# IO_board.net
KiCad netlist of a schematic drawn in Altium Designer
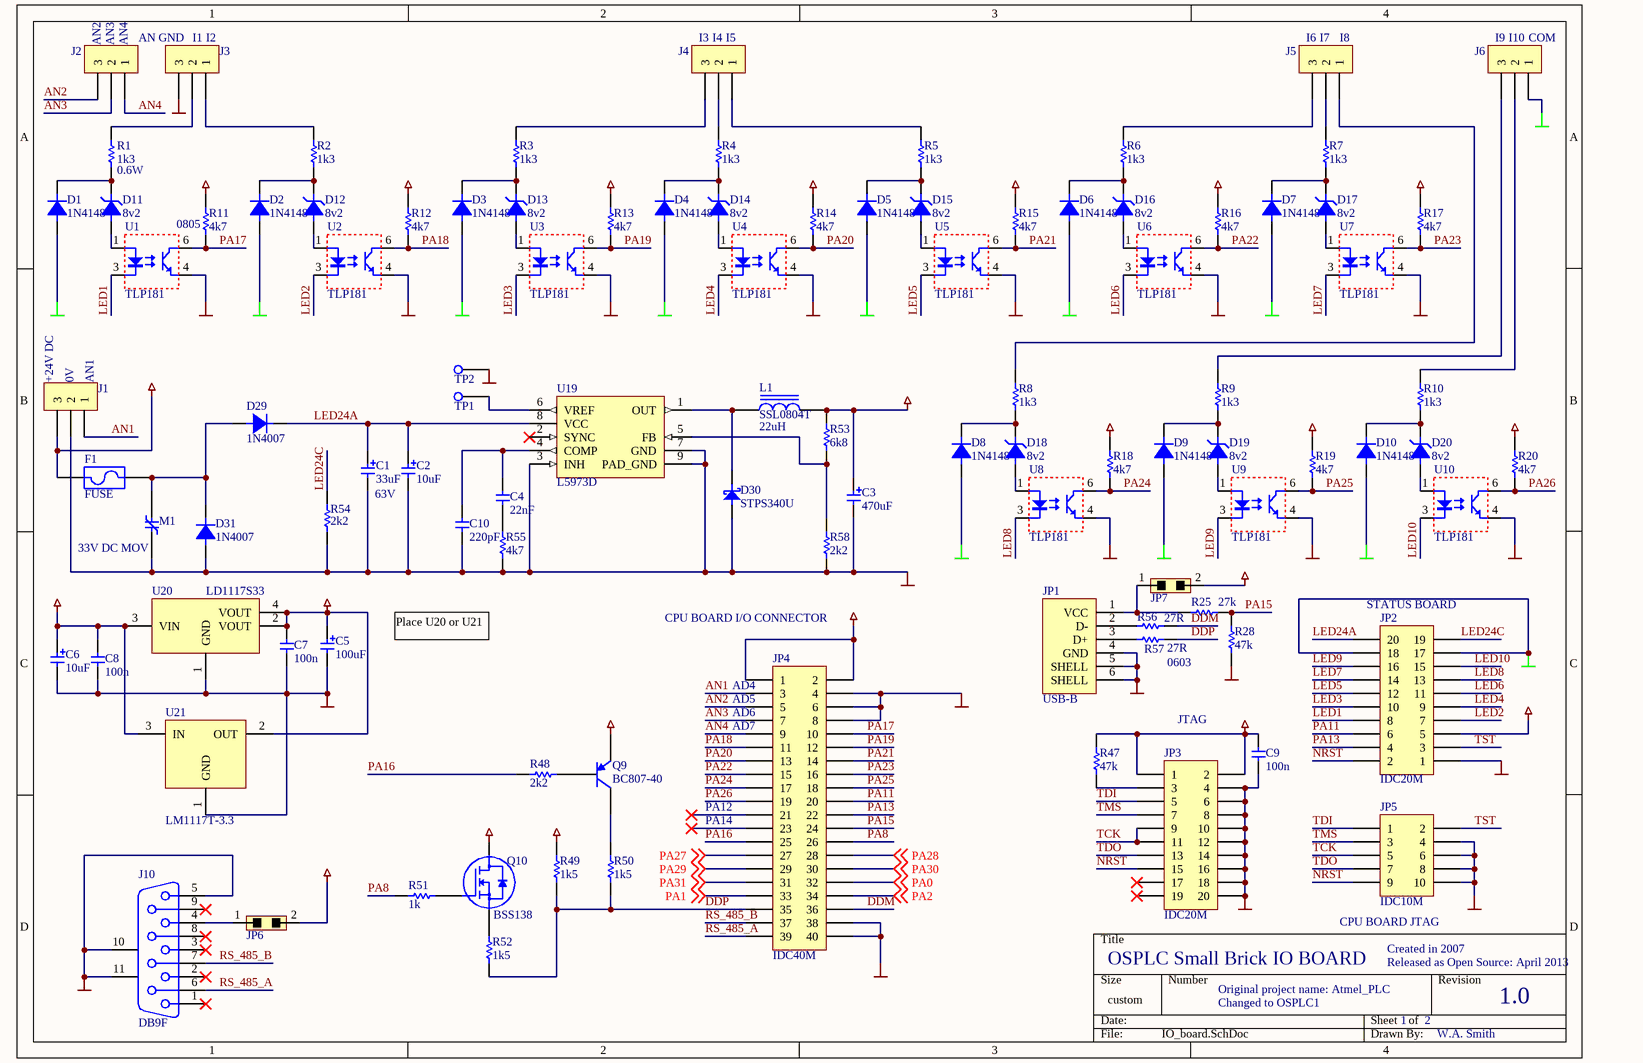
[diagram p0: IO_board.SchDoc]

(export (version "E")
  (design (tool "Eeschema 10.0.6"))
  (components
    (comp (ref "C1")
      (value "63V")
      (footprint "CAP_100_RP")
      (description "Electrolytic cap, 100 mil pitch")
      (fields (field (name "ALTIUM_VALUE") "33uF"))
      (libsource (lib "Integrated Comp_lib") (part "CAP_100_RP"))
    )
    (comp (ref "C2")
      (value "CAP_100_RP")
      (footprint "CAP_100_RP")
      (description "Electrolytic cap, 100 mil pitch")
      (fields (field (name "ALTIUM_VALUE") "10uF"))
      (libsource (lib "Integrated Comp_lib") (part "CAP_100_RP"))
    )
    (comp (ref "C3")
      (value "CAP_200_RP")
      (footprint "CAP_200_RP")
      (description "Radial Electrolytic Capacitor, 200 thou pin spacing")
      (fields (field (name "ALTIUM_VALUE") "470uF"))
      (libsource (lib "Integrated Comp_lib") (part "CAP_200_RP"))
    )
    (comp (ref "C4")
      (value "0805")
      (footprint "0805")
      (description "0805 footprint non-polarised capacitor")
      (fields (field (name "ALTIUM_VALUE") "22nF"))
      (libsource (lib "Integrated Comp_lib") (part "CAP_0805"))
    )
    (comp (ref "C5")
      (value "CAP_100_RP")
      (footprint "CAP_100_RP")
      (description "Electrolytic cap, 100 mil pitch")
      (fields (field (name "ALTIUM_VALUE") "100uF"))
      (libsource (lib "Integrated Comp_lib") (part "CAP_100_RP"))
    )
    (comp (ref "C6")
      (value "CAP_100_RP")
      (footprint "CAP_100_RP")
      (description "Electrolytic cap, 100 mil pitch")
      (fields (field (name "ALTIUM_VALUE") "10uF"))
      (libsource (lib "Integrated Comp_lib") (part "CAP_100_RP"))
    )
    (comp (ref "C7")
      (value "0805")
      (footprint "0805")
      (description "0805 footprint non-polarised capacitor")
      (fields (field (name "ALTIUM_VALUE") "100n"))
      (libsource (lib "Integrated Comp_lib") (part "CAP_0805"))
    )
    (comp (ref "C8")
      (value "0805")
      (footprint "0805")
      (description "0805 footprint non-polarised capacitor")
      (fields (field (name "ALTIUM_VALUE") "100n"))
      (libsource (lib "Integrated Comp_lib") (part "CAP_0805"))
    )
    (comp (ref "C9")
      (value "0603")
      (footprint "0603")
      (description "0603 footprint non-polorised capacitor")
      (fields (field (name "ALTIUM_VALUE") "100n"))
      (libsource (lib "Integrated Comp_lib") (part "CAP_0603"))
    )
    (comp (ref "C10")
      (value "0805")
      (footprint "0805")
      (description "0805 footprint non-polarised capacitor")
      (fields (field (name "ALTIUM_VALUE") "220pF"))
      (libsource (lib "Integrated Comp_lib") (part "CAP_0805"))
    )
    (comp (ref "D1")
      (value "1N4148_RAD")
      (footprint "DIODE_RAD_2.5MM")
      (description "Small signal diode")
      (fields (field (name "ALTIUM_VALUE") "1N4148"))
      (libsource (lib "ARM_projects") (part "1N4148"))
    )
    (comp (ref "D2")
      (value "1N4148_RAD")
      (footprint "DIODE_RAD_2.5MM")
      (description "Small signal diode")
      (fields (field (name "ALTIUM_VALUE") "1N4148"))
      (libsource (lib "ARM_projects") (part "1N4148"))
    )
    (comp (ref "D3")
      (value "1N4148_RAD")
      (footprint "DIODE_RAD_2.5MM")
      (description "Small signal diode")
      (fields (field (name "ALTIUM_VALUE") "1N4148"))
      (libsource (lib "ARM_projects") (part "1N4148"))
    )
    (comp (ref "D4")
      (value "1N4148_RAD")
      (footprint "DIODE_RAD_2.5MM")
      (description "Small signal diode")
      (fields (field (name "ALTIUM_VALUE") "1N4148"))
      (libsource (lib "ARM_projects") (part "1N4148"))
    )
    (comp (ref "D5")
      (value "1N4148_RAD")
      (footprint "DIODE_RAD_2.5MM")
      (description "Small signal diode")
      (fields (field (name "ALTIUM_VALUE") "1N4148"))
      (libsource (lib "ARM_projects") (part "1N4148"))
    )
    (comp (ref "D6")
      (value "1N4148_RAD")
      (footprint "DIODE_RAD_2.5MM")
      (description "Small signal diode")
      (fields (field (name "ALTIUM_VALUE") "1N4148"))
      (libsource (lib "ARM_projects") (part "1N4148"))
    )
    (comp (ref "D7")
      (value "1N4148_RAD")
      (footprint "DIODE_RAD_2.5MM")
      (description "Small signal diode")
      (fields (field (name "ALTIUM_VALUE") "1N4148"))
      (libsource (lib "ARM_projects") (part "1N4148"))
    )
    (comp (ref "D8")
      (value "1N4148_RAD")
      (footprint "DIODE_RAD_2.5MM")
      (description "Small signal diode")
      (fields (field (name "ALTIUM_VALUE") "1N4148"))
      (libsource (lib "ARM_projects") (part "1N4148"))
    )
    (comp (ref "D9")
      (value "1N4148_RAD")
      (footprint "DIODE_RAD_2.5MM")
      (description "Small signal diode")
      (fields (field (name "ALTIUM_VALUE") "1N4148"))
      (libsource (lib "ARM_projects") (part "1N4148"))
    )
    (comp (ref "D10")
      (value "1N4148_RAD")
      (footprint "DIODE_RAD_2.5MM")
      (description "Small signal diode")
      (fields (field (name "ALTIUM_VALUE") "1N4148"))
      (libsource (lib "ARM_projects") (part "1N4148"))
    )
    (comp (ref "D11")
      (value "500mW Zener")
      (footprint "DIODE_RAD_2.5MM")
      (description "500mW Zener Diode")
      (fields (field (name "ALTIUM_VALUE") "8v2"))
      (libsource (lib "ARM_projects") (part "ZENDER_500MW"))
    )
    (comp (ref "D12")
      (value "500mW Zener")
      (footprint "DIODE_RAD_2.5MM")
      (description "500mW Zener Diode")
      (fields (field (name "ALTIUM_VALUE") "8v2"))
      (libsource (lib "ARM_projects") (part "ZENDER_500MW"))
    )
    (comp (ref "D13")
      (value "500mW Zener")
      (footprint "DIODE_RAD_2.5MM")
      (description "500mW Zener Diode")
      (fields (field (name "ALTIUM_VALUE") "8v2"))
      (libsource (lib "ARM_projects") (part "ZENDER_500MW"))
    )
    (comp (ref "D14")
      (value "500mW Zener")
      (footprint "DIODE_RAD_2.5MM")
      (description "500mW Zener Diode")
      (fields (field (name "ALTIUM_VALUE") "8v2"))
      (libsource (lib "ARM_projects") (part "ZENDER_500MW"))
    )
    (comp (ref "D15")
      (value "500mW Zener")
      (footprint "DIODE_RAD_2.5MM")
      (description "500mW Zener Diode")
      (fields (field (name "ALTIUM_VALUE") "8v2"))
      (libsource (lib "ARM_projects") (part "ZENDER_500MW"))
    )
    (comp (ref "D16")
      (value "500mW Zener")
      (footprint "DIODE_RAD_2.5MM")
      (description "500mW Zener Diode")
      (fields (field (name "ALTIUM_VALUE") "8v2"))
      (libsource (lib "ARM_projects") (part "ZENDER_500MW"))
    )
    (comp (ref "D17")
      (value "500mW Zener")
      (footprint "DIODE_RAD_2.5MM")
      (description "500mW Zener Diode")
      (fields (field (name "ALTIUM_VALUE") "8v2"))
      (libsource (lib "ARM_projects") (part "ZENDER_500MW"))
    )
    (comp (ref "D18")
      (value "500mW Zener")
      (footprint "DIODE_RAD_2.5MM")
      (description "500mW Zener Diode")
      (fields (field (name "ALTIUM_VALUE") "8v2"))
      (libsource (lib "ARM_projects") (part "ZENDER_500MW"))
    )
    (comp (ref "D19")
      (value "500mW Zener")
      (footprint "DIODE_RAD_2.5MM")
      (description "500mW Zener Diode")
      (fields (field (name "ALTIUM_VALUE") "8v2"))
      (libsource (lib "ARM_projects") (part "ZENDER_500MW"))
    )
    (comp (ref "D20")
      (value "500mW Zener")
      (footprint "DIODE_RAD_2.5MM")
      (description "500mW Zener Diode")
      (fields (field (name "ALTIUM_VALUE") "8v2"))
      (libsource (lib "ARM_projects") (part "ZENDER_500MW"))
    )
    (comp (ref "D29")
      (value "1N4007 Radialy Mounted")
      (footprint "DIODE_RAD_3MM")
      (description "1N4007 Rectifier Diode Radialy Mounted")
      (fields (field (name "ALTIUM_VALUE") "1N4007"))
      (libsource (lib "ARM_projects") (part "1N4007"))
    )
    (comp (ref "D30")
      (value "STPS340U")
      (footprint "STPS2L25U")
      (description "Power Schottky rectifier, ST")
      (libsource (lib "ARM_projects") (part "STPS340U"))
    )
    (comp (ref "D31")
      (value "1N4007 Radialy Mounted")
      (footprint "DIODE_RAD_3MM")
      (description "1N4007 Rectifier Diode Radialy Mounted")
      (fields (field (name "ALTIUM_VALUE") "1N4007"))
      (libsource (lib "ARM_projects") (part "1N4007"))
    )
    (comp (ref "F1")
      (value "FUSE")
      (footprint "FUSE_5X20")
      (description "5mm by 20mm Fuse")
      (libsource (lib "ARM_projects") (part "FUSE_5X20"))
    )
    (comp (ref "J1")
      (value "PCB TERMINAL")
      (footprint "TERMINAL_3WAY_5MM")
      (description "5mm spaced PCB terminal, 3 pole")
      (libsource (lib "ARM_projects") (part "TERMINAL_3WAY_5MM"))
    )
    (comp (ref "J2")
      (value "PCB TERMINAL")
      (footprint "TERMINAL_3WAY_5MM")
      (description "5mm spaced PCB terminal, 3 pole")
      (libsource (lib "ARM_projects") (part "TERMINAL_3WAY_5MM"))
    )
    (comp (ref "J3")
      (value "PCB TERMINAL")
      (footprint "TERMINAL_3WAY_5MM")
      (description "5mm spaced PCB terminal, 3 pole")
      (libsource (lib "ARM_projects") (part "TERMINAL_3WAY_5MM"))
    )
    (comp (ref "J4")
      (value "PCB TERMINAL")
      (footprint "TERMINAL_3WAY_5MM")
      (description "5mm spaced PCB terminal, 3 pole")
      (libsource (lib "ARM_projects") (part "TERMINAL_3WAY_5MM"))
    )
    (comp (ref "J5")
      (value "PCB TERMINAL")
      (footprint "TERMINAL_3WAY_5MM")
      (description "5mm spaced PCB terminal, 3 pole")
      (libsource (lib "ARM_projects") (part "TERMINAL_3WAY_5MM"))
    )
    (comp (ref "J6")
      (value "PCB TERMINAL")
      (footprint "TERMINAL_3WAY_5MM")
      (description "5mm spaced PCB terminal, 3 pole")
      (libsource (lib "ARM_projects") (part "TERMINAL_3WAY_5MM"))
    )
    (comp (ref "J10")
      (value "DB9F")
      (footprint "DSUB1.385-2H9")
      (description "Receptacle Assembly, 9 Position, Right Angle")
      (fields (field (name "MANUFACTURER") "Generic Components") (field (name "PUBLISHER") "Altium Limited"))
      (libsource (lib "Miscellaneous Connectors") (part "D Connector 9"))
    )
    (comp (ref "JP1")
      (value "USB-B")
      (footprint "USB_B_VERT")
      (description "Vertically mounting USB type B connector")
      (libsource (lib "ARM_projects") (part "USB_B_VERT"))
    )
    (comp (ref "JP2")
      (value "IDC20M")
      (footprint "IDC_20M_BOX")
      (description "20 pin IDC male connector, vertical, box")
      (libsource (lib "ARM_projects") (part "IDC_20M"))
    )
    (comp (ref "JP3")
      (value "IDC20M")
      (footprint "IDC_20M_BOX")
      (description "20 pin IDC male connector, vertical, box")
      (libsource (lib "") (part "IDC_20M_1"))
    )
    (comp (ref "JP4")
      (value "IDC40M")
      (footprint "IDC_40M_BOX")
      (description "40 pin IDC male connector, vertical, box")
      (libsource (lib "Integrated Comp_lib") (part "IDC_40M"))
    )
    (comp (ref "JP5")
      (value "IDC10M")
      (footprint "IDC_10M_BOX")
      (description "10 pin IDC male connector, vertical, box")
      (libsource (lib "Integrated Comp_lib") (part "IDC_10M"))
    )
    (comp (ref "JP6")
      (value "JUMPER2")
      (footprint "JUMPER2_254")
      (description "2 Pin Jumper, 2.54mm")
      (libsource (lib "ARM_projects") (part "JUMPER2"))
    )
    (comp (ref "JP7")
      (value "JUMPER2")
      (footprint "JUMPER2_254")
      (description "2 Pin Jumper, 2.54mm")
      (libsource (lib "ARM_projects") (part "JUMPER2"))
    )
    (comp (ref "L1")
      (value "SSL0804T")
      (footprint "SSL0804")
      (description "Yageo SMD Power Inductor")
      (fields (field (name "ALTIUM_UNNAMED_1") "22uH"))
      (libsource (lib "ARM_projects") (part "SSL0804T"))
    )
    (comp (ref "M1")
      (value "33V DC MOV")
      (footprint "MOV_7.6mm")
      (description "Metal Oxide Varistor")
      (libsource (lib "ARM_projects") (part "MOV_7.6MM"))
    )
    (comp (ref "Q9")
      (value "BC807-40")
      (footprint "SO-G3/Y1")
      (description "PNP General Purpose Amplifier")
      (fields
        (field (name "MANUFACTURER") "Fairchild Semiconductor")
        (field (name "PUBLISHER") "Altium Limited")
      )
      (libsource (lib "FSC Discrete BJT") (part "BC807-40"))
    )
    (comp (ref "Q10")
      (value "BSS138")
      (footprint "SOT-23")
      (description "Fairchild, N-channel MOSFET")
      (libsource (lib "Integrated Comp_lib") (part "BSS138"))
    )
    (comp (ref "R1")
      (value "0.6W")
      (footprint "RADIAL3MM")
      (description "Radialy mounted resistor")
      (fields (field (name "ALTIUM_VALUE") "1k3"))
      (libsource (lib "ARM_projects") (part "RES_RADIAL_3MM"))
    )
    (comp (ref "R2")
      (value "RES_RADIAL_3MM")
      (footprint "RADIAL3MM")
      (description "Radialy mounted resistor")
      (fields (field (name "ALTIUM_VALUE") "1k3"))
      (libsource (lib "ARM_projects") (part "RES_RADIAL_3MM"))
    )
    (comp (ref "R3")
      (value "RES_RADIAL_3MM")
      (footprint "RADIAL3MM")
      (description "Radialy mounted resistor")
      (fields (field (name "ALTIUM_VALUE") "1k3"))
      (libsource (lib "ARM_projects") (part "RES_RADIAL_3MM"))
    )
    (comp (ref "R4")
      (value "RES_RADIAL_3MM")
      (footprint "RADIAL3MM")
      (description "Radialy mounted resistor")
      (fields (field (name "ALTIUM_VALUE") "1k3"))
      (libsource (lib "ARM_projects") (part "RES_RADIAL_3MM"))
    )
    (comp (ref "R5")
      (value "RES_RADIAL_3MM")
      (footprint "RADIAL3MM")
      (description "Radialy mounted resistor")
      (fields (field (name "ALTIUM_VALUE") "1k3"))
      (libsource (lib "ARM_projects") (part "RES_RADIAL_3MM"))
    )
    (comp (ref "R6")
      (value "RES_RADIAL_3MM")
      (footprint "RADIAL3MM")
      (description "Radialy mounted resistor")
      (fields (field (name "ALTIUM_VALUE") "1k3"))
      (libsource (lib "ARM_projects") (part "RES_RADIAL_3MM"))
    )
    (comp (ref "R7")
      (value "RES_RADIAL_3MM")
      (footprint "RADIAL3MM")
      (description "Radialy mounted resistor")
      (fields (field (name "ALTIUM_VALUE") "1k3"))
      (libsource (lib "ARM_projects") (part "RES_RADIAL_3MM"))
    )
    (comp (ref "R8")
      (value "RES_RADIAL_3MM")
      (footprint "RADIAL3MM")
      (description "Radialy mounted resistor")
      (fields (field (name "ALTIUM_VALUE") "1k3"))
      (libsource (lib "ARM_projects") (part "RES_RADIAL_3MM"))
    )
    (comp (ref "R9")
      (value "RES_RADIAL_3MM")
      (footprint "RADIAL3MM")
      (description "Radialy mounted resistor")
      (fields (field (name "ALTIUM_VALUE") "1k3"))
      (libsource (lib "ARM_projects") (part "RES_RADIAL_3MM"))
    )
    (comp (ref "R10")
      (value "RES_RADIAL_3MM")
      (footprint "RADIAL3MM")
      (description "Radialy mounted resistor")
      (fields (field (name "ALTIUM_VALUE") "1k3"))
      (libsource (lib "ARM_projects") (part "RES_RADIAL_3MM"))
    )
    (comp (ref "R11")
      (value "0805")
      (footprint "0805")
      (description "0805 footprint resistor")
      (fields (field (name "ALTIUM_VALUE") "4k7"))
      (libsource (lib "Integrated Comp_lib") (part "RES_0805"))
    )
    (comp (ref "R12")
      (value "0805")
      (footprint "0805")
      (description "0805 footprint resistor")
      (fields (field (name "ALTIUM_VALUE") "4k7"))
      (libsource (lib "Integrated Comp_lib") (part "RES_0805"))
    )
    (comp (ref "R13")
      (value "0805")
      (footprint "0805")
      (description "0805 footprint resistor")
      (fields (field (name "ALTIUM_VALUE") "4k7"))
      (libsource (lib "Integrated Comp_lib") (part "RES_0805"))
    )
    (comp (ref "R14")
      (value "0805")
      (footprint "0805")
      (description "0805 footprint resistor")
      (fields (field (name "ALTIUM_VALUE") "4k7"))
      (libsource (lib "Integrated Comp_lib") (part "RES_0805"))
    )
    (comp (ref "R15")
      (value "0805")
      (footprint "0805")
      (description "0805 footprint resistor")
      (fields (field (name "ALTIUM_VALUE") "4k7"))
      (libsource (lib "Integrated Comp_lib") (part "RES_0805"))
    )
    (comp (ref "R16")
      (value "0805")
      (footprint "0805")
      (description "0805 footprint resistor")
      (fields (field (name "ALTIUM_VALUE") "4k7"))
      (libsource (lib "Integrated Comp_lib") (part "RES_0805"))
    )
    (comp (ref "R17")
      (value "0805")
      (footprint "0805")
      (description "0805 footprint resistor")
      (fields (field (name "ALTIUM_VALUE") "4k7"))
      (libsource (lib "Integrated Comp_lib") (part "RES_0805"))
    )
    (comp (ref "R18")
      (value "0805")
      (footprint "0805")
      (description "0805 footprint resistor")
      (fields (field (name "ALTIUM_VALUE") "4k7"))
      (libsource (lib "Integrated Comp_lib") (part "RES_0805"))
    )
    (comp (ref "R19")
      (value "0805")
      (footprint "0805")
      (description "0805 footprint resistor")
      (fields (field (name "ALTIUM_VALUE") "4k7"))
      (libsource (lib "Integrated Comp_lib") (part "RES_0805"))
    )
    (comp (ref "R20")
      (value "0805")
      (footprint "0805")
      (description "0805 footprint resistor")
      (fields (field (name "ALTIUM_VALUE") "4k7"))
      (libsource (lib "Integrated Comp_lib") (part "RES_0805"))
    )
    (comp (ref "R25")
      (value "0805")
      (footprint "0805")
      (description "0805 footprint resistor")
      (fields (field (name "ALTIUM_VALUE") "27k"))
      (libsource (lib "Integrated Comp_lib") (part "RES_0805"))
    )
    (comp (ref "R28")
      (value "0805")
      (footprint "0805")
      (description "0805 footprint resistor")
      (fields (field (name "ALTIUM_VALUE") "47k"))
      (libsource (lib "Integrated Comp_lib") (part "RES_0805"))
    )
    (comp (ref "R47")
      (value "0805")
      (footprint "0805")
      (description "0805 footprint resistor")
      (fields (field (name "ALTIUM_VALUE") "47k"))
      (libsource (lib "Integrated Comp_lib") (part "RES_0805"))
    )
    (comp (ref "R48")
      (value "0805")
      (footprint "0805")
      (description "0805 footprint resistor")
      (fields (field (name "ALTIUM_VALUE") "2k2"))
      (libsource (lib "Integrated Comp_lib") (part "RES_0805"))
    )
    (comp (ref "R49")
      (value "0805")
      (footprint "0805")
      (description "0805 footprint resistor")
      (fields (field (name "ALTIUM_VALUE") "1k5"))
      (libsource (lib "Integrated Comp_lib") (part "RES_0805"))
    )
    (comp (ref "R50")
      (value "0805")
      (footprint "0805")
      (description "0805 footprint resistor")
      (fields (field (name "ALTIUM_VALUE") "1k5"))
      (libsource (lib "Integrated Comp_lib") (part "RES_0805"))
    )
    (comp (ref "R51")
      (value "0805")
      (footprint "0805")
      (description "0805 footprint resistor")
      (fields (field (name "ALTIUM_VALUE") "1k"))
      (libsource (lib "Integrated Comp_lib") (part "RES_0805"))
    )
    (comp (ref "R52")
      (value "0805")
      (footprint "0805")
      (description "0805 footprint resistor")
      (fields (field (name "ALTIUM_VALUE") "1k5"))
      (libsource (lib "Integrated Comp_lib") (part "RES_0805"))
    )
    (comp (ref "R53")
      (value "0805")
      (footprint "0805")
      (description "0805 footprint resistor")
      (fields (field (name "ALTIUM_VALUE") "6k8"))
      (libsource (lib "Integrated Comp_lib") (part "RES_0805"))
    )
    (comp (ref "R54")
      (value "Res1")
      (footprint "AXIAL-0.3")
      (description "Resistor")
      (fields
        (field (name "MANUFACTURER") "Generic Components")
        (field (name "ALTIUM_VALUE") "2k2")
        (field (name "PUBLISHER") "Altium Limited")
      )
      (libsource (lib "Miscellaneous Devices") (part "Res1"))
    )
    (comp (ref "R55")
      (value "0805")
      (footprint "0805")
      (description "0805 footprint resistor")
      (fields (field (name "ALTIUM_VALUE") "4k7"))
      (libsource (lib "Integrated Comp_lib") (part "RES_0805"))
    )
    (comp (ref "R56")
      (value "0603")
      (footprint "0603")
      (description "0603 footprint resistor")
      (fields (field (name "ALTIUM_VALUE") "27R"))
      (libsource (lib "Integrated Comp_lib") (part "RES_0603"))
    )
    (comp (ref "R57")
      (value "0603")
      (footprint "0603")
      (description "0603 footprint resistor")
      (fields (field (name "ALTIUM_VALUE") "27R"))
      (libsource (lib "Integrated Comp_lib") (part "RES_0603"))
    )
    (comp (ref "R58")
      (value "0805")
      (footprint "0805")
      (description "0805 footprint resistor")
      (fields (field (name "ALTIUM_VALUE") "2k2"))
      (libsource (lib "Integrated Comp_lib") (part "RES_0805"))
    )
    (comp (ref "TP1")
      (value "TEST POINT")
      (footprint "TEST_POINT_TH")
      (description "Through hole test point")
      (libsource (lib "ARM_projects") (part "TEST_POINT_TH"))
    )
    (comp (ref "TP2")
      (value "TEST POINT")
      (footprint "TEST_POINT_TH")
      (description "Through hole test point")
      (libsource (lib "ARM_projects") (part "TEST_POINT_TH"))
    )
    (comp (ref "U1")
      (value "TLP181")
      (footprint "SOP4_2.54")
      (description "Toshiba Photocoupler")
      (libsource (lib "Integrated Comp_lib") (part "TLP181"))
    )
    (comp (ref "U2")
      (value "TLP181")
      (footprint "SOP4_2.54")
      (description "Toshiba Photocoupler")
      (libsource (lib "Integrated Comp_lib") (part "TLP181"))
    )
    (comp (ref "U3")
      (value "TLP181")
      (footprint "SOP4_2.54")
      (description "Toshiba Photocoupler")
      (libsource (lib "Integrated Comp_lib") (part "TLP181"))
    )
    (comp (ref "U4")
      (value "TLP181")
      (footprint "SOP4_2.54")
      (description "Toshiba Photocoupler")
      (libsource (lib "Integrated Comp_lib") (part "TLP181"))
    )
    (comp (ref "U5")
      (value "TLP181")
      (footprint "SOP4_2.54")
      (description "Toshiba Photocoupler")
      (libsource (lib "Integrated Comp_lib") (part "TLP181"))
    )
    (comp (ref "U6")
      (value "TLP181")
      (footprint "SOP4_2.54")
      (description "Toshiba Photocoupler")
      (libsource (lib "Integrated Comp_lib") (part "TLP181"))
    )
    (comp (ref "U7")
      (value "TLP181")
      (footprint "SOP4_2.54")
      (description "Toshiba Photocoupler")
      (libsource (lib "Integrated Comp_lib") (part "TLP181"))
    )
    (comp (ref "U8")
      (value "TLP181")
      (footprint "SOP4_2.54")
      (description "Toshiba Photocoupler")
      (libsource (lib "Integrated Comp_lib") (part "TLP181"))
    )
    (comp (ref "U9")
      (value "TLP181")
      (footprint "SOP4_2.54")
      (description "Toshiba Photocoupler")
      (libsource (lib "Integrated Comp_lib") (part "TLP181"))
    )
    (comp (ref "U10")
      (value "TLP181")
      (footprint "SOP4_2.54")
      (description "Toshiba Photocoupler")
      (libsource (lib "Integrated Comp_lib") (part "TLP181"))
    )
    (comp (ref "U19")
      (value "L5973D")
      (footprint "ARM_projects:HSOP8")
      (description "ST 2.5A switch step down switching regulator")
      (libsource (lib "ARM_projects") (part "L5973D"))
    )
    (comp (ref "U20")
      (value "LD1117S33")
      (footprint "SOT-223")
      (description "ST 3.3V LDO regulator")
      (libsource (lib "ARM_projects") (part "LD1117S33"))
    )
    (comp (ref "U21")
      (value "LM1117T-3.3")
      (footprint "TO220")
      (description "3.3V Regulator, 800mA, Vertical Mounted")
      (libsource (lib "ARM_projects") (part "LM1117T3.3_VERT"))
    )
  )
  (nets
    (net (code "1") (name "/AN1") (class "Default")
      (node (ref "J1") (pin "1") (pinfunction "1_1") (pintype "passive"))
      (node (ref "JP4") (pin "3") (pinfunction "3_3") (pintype "passive"))
    )
    (net (code "2") (name "/AN2") (class "Default")
      (node (ref "J2") (pin "3") (pinfunction "3_3") (pintype "passive"))
      (node (ref "JP4") (pin "5") (pinfunction "5_5") (pintype "passive"))
    )
    (net (code "3") (name "/AN3") (class "Default")
      (node (ref "J2") (pin "2") (pinfunction "2_2") (pintype "passive"))
      (node (ref "JP4") (pin "7") (pinfunction "7_7") (pintype "passive"))
    )
    (net (code "4") (name "/AN4") (class "Default")
      (node (ref "J2") (pin "1") (pinfunction "1_1") (pintype "passive"))
      (node (ref "JP4") (pin "9") (pinfunction "9_9") (pintype "passive"))
    )
    (net (code "5") (name "/DDM") (class "Default")
      (node (ref "JP4") (pin "36") (pinfunction "36_36") (pintype "passive"))
      (node (ref "R56") (pin "2") (pinfunction "2_2") (pintype "passive"))
    )
    (net (code "6") (name "/DDP") (class "Default")
      (node (ref "JP4") (pin "35") (pinfunction "35_35") (pintype "passive"))
      (node (ref "R49") (pin "1") (pinfunction "1_1") (pintype "passive"))
      (node (ref "R50") (pin "1") (pinfunction "1_1") (pintype "passive"))
      (node (ref "R52") (pin "1") (pinfunction "1_1") (pintype "passive"))
      (node (ref "R57") (pin "2") (pinfunction "2_2") (pintype "passive"))
    )
    (net (code "7") (name "/LED1") (class "Default")
      (node (ref "JP2") (pin "8") (pinfunction "8_8") (pintype "passive"))
      (node (ref "U1") (pin "3") (pinfunction "3_3") (pintype "passive"))
    )
    (net (code "8") (name "/LED2") (class "Default")
      (node (ref "JP2") (pin "7") (pinfunction "7_7") (pintype "passive"))
      (node (ref "U2") (pin "3") (pinfunction "3_3") (pintype "passive"))
    )
    (net (code "9") (name "/LED3") (class "Default")
      (node (ref "JP2") (pin "10") (pinfunction "10_10") (pintype "passive"))
      (node (ref "U3") (pin "3") (pinfunction "3_3") (pintype "passive"))
    )
    (net (code "10") (name "/LED4") (class "Default")
      (node (ref "JP2") (pin "9") (pinfunction "9_9") (pintype "passive"))
      (node (ref "U4") (pin "3") (pinfunction "3_3") (pintype "passive"))
    )
    (net (code "11") (name "/LED5") (class "Default")
      (node (ref "JP2") (pin "12") (pinfunction "12_12") (pintype "passive"))
      (node (ref "U5") (pin "3") (pinfunction "3_3") (pintype "passive"))
    )
    (net (code "12") (name "/LED6") (class "Default")
      (node (ref "JP2") (pin "11") (pinfunction "11_11") (pintype "passive"))
      (node (ref "U6") (pin "3") (pinfunction "3_3") (pintype "passive"))
    )
    (net (code "13") (name "/LED7") (class "Default")
      (node (ref "JP2") (pin "14") (pinfunction "14_14") (pintype "passive"))
      (node (ref "U7") (pin "3") (pinfunction "3_3") (pintype "passive"))
    )
    (net (code "14") (name "/LED8") (class "Default")
      (node (ref "JP2") (pin "13") (pinfunction "13_13") (pintype "passive"))
      (node (ref "U8") (pin "3") (pinfunction "3_3") (pintype "passive"))
    )
    (net (code "15") (name "/LED9") (class "Default")
      (node (ref "JP2") (pin "16") (pinfunction "16_16") (pintype "passive"))
      (node (ref "U9") (pin "3") (pinfunction "3_3") (pintype "passive"))
    )
    (net (code "16") (name "/LED10") (class "Default")
      (node (ref "JP2") (pin "15") (pinfunction "15_15") (pintype "passive"))
      (node (ref "U10") (pin "3") (pinfunction "3_3") (pintype "passive"))
    )
    (net (code "17") (name "/LED24A") (class "Default")
      (node (ref "C1") (pin "1") (pinfunction "1_1") (pintype "passive"))
      (node (ref "C2") (pin "1") (pinfunction "1_1") (pintype "passive"))
      (node (ref "D29") (pin "1") (pinfunction "C_1") (pintype "passive"))
      (node (ref "JP2") (pin "20") (pinfunction "20_20") (pintype "passive"))
      (node (ref "U19") (pin "8") (pinfunction "VCC_8") (pintype "power_in"))
    )
    (net (code "18") (name "/LED24C") (class "Default")
      (node (ref "JP2") (pin "19") (pinfunction "19_19") (pintype "passive"))
      (node (ref "R54") (pin "2") (pinfunction "2_2") (pintype "passive"))
    )
    (net (code "19") (name "/NRST") (class "Default")
      (node (ref "JP2") (pin "2") (pinfunction "2_2") (pintype "passive"))
      (node (ref "JP3") (pin "15") (pinfunction "15_15") (pintype "passive"))
      (node (ref "JP5") (pin "9") (pinfunction "9_9") (pintype "passive"))
    )
    (net (code "20") (name "/PA8") (class "Default")
      (node (ref "JP4") (pin "26") (pinfunction "26_26") (pintype "passive"))
      (node (ref "R51") (pin "1") (pinfunction "1_1") (pintype "passive"))
    )
    (net (code "21") (name "/PA11") (class "Default")
      (node (ref "JP2") (pin "6") (pinfunction "6_6") (pintype "passive"))
      (node (ref "JP4") (pin "20") (pinfunction "20_20") (pintype "passive"))
    )
    (net (code "22") (name "/PA13") (class "Default")
      (node (ref "JP2") (pin "4") (pinfunction "4_4") (pintype "passive"))
      (node (ref "JP4") (pin "22") (pinfunction "22_22") (pintype "passive"))
    )
    (net (code "23") (name "/PA15") (class "Default")
      (node (ref "JP4") (pin "24") (pinfunction "24_24") (pintype "passive"))
      (node (ref "R25") (pin "2") (pinfunction "2_2") (pintype "passive"))
      (node (ref "R28") (pin "2") (pinfunction "2_2") (pintype "passive"))
    )
    (net (code "24") (name "/PA16") (class "Default")
      (node (ref "JP4") (pin "25") (pinfunction "25_25") (pintype "passive"))
      (node (ref "R48") (pin "1") (pinfunction "1_1") (pintype "passive"))
    )
    (net (code "25") (name "/PA17") (class "Default")
      (node (ref "JP4") (pin "10") (pinfunction "10_10") (pintype "passive"))
      (node (ref "R11") (pin "1") (pinfunction "1_1") (pintype "passive"))
      (node (ref "U1") (pin "6") (pinfunction "6_6") (pintype "passive"))
    )
    (net (code "26") (name "/PA18") (class "Default")
      (node (ref "JP4") (pin "11") (pinfunction "11_11") (pintype "passive"))
      (node (ref "R12") (pin "1") (pinfunction "1_1") (pintype "passive"))
      (node (ref "U2") (pin "6") (pinfunction "6_6") (pintype "passive"))
    )
    (net (code "27") (name "/PA19") (class "Default")
      (node (ref "JP4") (pin "12") (pinfunction "12_12") (pintype "passive"))
      (node (ref "R13") (pin "1") (pinfunction "1_1") (pintype "passive"))
      (node (ref "U3") (pin "6") (pinfunction "6_6") (pintype "passive"))
    )
    (net (code "28") (name "/PA20") (class "Default")
      (node (ref "JP4") (pin "13") (pinfunction "13_13") (pintype "passive"))
      (node (ref "R14") (pin "1") (pinfunction "1_1") (pintype "passive"))
      (node (ref "U4") (pin "6") (pinfunction "6_6") (pintype "passive"))
    )
    (net (code "29") (name "/PA21") (class "Default")
      (node (ref "JP4") (pin "14") (pinfunction "14_14") (pintype "passive"))
      (node (ref "R15") (pin "1") (pinfunction "1_1") (pintype "passive"))
      (node (ref "U5") (pin "6") (pinfunction "6_6") (pintype "passive"))
    )
    (net (code "30") (name "/PA22") (class "Default")
      (node (ref "JP4") (pin "15") (pinfunction "15_15") (pintype "passive"))
      (node (ref "R16") (pin "1") (pinfunction "1_1") (pintype "passive"))
      (node (ref "U6") (pin "6") (pinfunction "6_6") (pintype "passive"))
    )
    (net (code "31") (name "/PA23") (class "Default")
      (node (ref "JP4") (pin "16") (pinfunction "16_16") (pintype "passive"))
      (node (ref "R17") (pin "1") (pinfunction "1_1") (pintype "passive"))
      (node (ref "U7") (pin "6") (pinfunction "6_6") (pintype "passive"))
    )
    (net (code "32") (name "/PA24") (class "Default")
      (node (ref "JP4") (pin "17") (pinfunction "17_17") (pintype "passive"))
      (node (ref "R18") (pin "1") (pinfunction "1_1") (pintype "passive"))
      (node (ref "U8") (pin "6") (pinfunction "6_6") (pintype "passive"))
    )
    (net (code "33") (name "/PA25") (class "Default")
      (node (ref "JP4") (pin "18") (pinfunction "18_18") (pintype "passive"))
      (node (ref "R19") (pin "1") (pinfunction "1_1") (pintype "passive"))
      (node (ref "U9") (pin "6") (pinfunction "6_6") (pintype "passive"))
    )
    (net (code "34") (name "/PA26") (class "Default")
      (node (ref "JP4") (pin "19") (pinfunction "19_19") (pintype "passive"))
      (node (ref "R20") (pin "1") (pinfunction "1_1") (pintype "passive"))
      (node (ref "U10") (pin "6") (pinfunction "6_6") (pintype "passive"))
    )
    (net (code "35") (name "/RS_485_A") (class "Default")
      (node (ref "J10") (pin "6") (pinfunction "6_6") (pintype "passive"))
      (node (ref "JP4") (pin "39") (pinfunction "39_39") (pintype "passive"))
    )
    (net (code "36") (name "/RS_485_B") (class "Default")
      (node (ref "J10") (pin "7") (pinfunction "7_7") (pintype "passive"))
      (node (ref "JP4") (pin "37") (pinfunction "37_37") (pintype "passive"))
    )
    (net (code "37") (name "/TCK") (class "Default")
      (node (ref "JP3") (pin "11") (pinfunction "11_11") (pintype "passive"))
      (node (ref "JP3") (pin "9") (pinfunction "9_9") (pintype "passive"))
      (node (ref "JP5") (pin "5") (pinfunction "5_5") (pintype "passive"))
    )
    (net (code "38") (name "/TDI") (class "Default")
      (node (ref "JP3") (pin "5") (pinfunction "5_5") (pintype "passive"))
      (node (ref "JP5") (pin "1") (pinfunction "1_1") (pintype "passive"))
    )
    (net (code "39") (name "/TDO") (class "Default")
      (node (ref "JP3") (pin "13") (pinfunction "13_13") (pintype "passive"))
      (node (ref "JP5") (pin "7") (pinfunction "7_7") (pintype "passive"))
    )
    (net (code "40") (name "/TMS") (class "Default")
      (node (ref "JP3") (pin "7") (pinfunction "7_7") (pintype "passive"))
      (node (ref "JP5") (pin "3") (pinfunction "3_3") (pintype "passive"))
    )
    (net (code "41") (name "/TST") (class "Default")
      (node (ref "JP2") (pin "3") (pinfunction "3_3") (pintype "passive"))
      (node (ref "JP5") (pin "2") (pinfunction "2_2") (pintype "passive"))
    )
    (net (code "42") (name "GND") (class "Default")
      (node (ref "C1") (pin "2") (pinfunction "2_2") (pintype "passive"))
      (node (ref "C10") (pin "1") (pinfunction "1_1") (pintype "passive"))
      (node (ref "C2") (pin "2") (pinfunction "2_2") (pintype "passive"))
      (node (ref "C3") (pin "2") (pinfunction "2_2") (pintype "passive"))
      (node (ref "C5") (pin "2") (pinfunction "2_2") (pintype "passive"))
      (node (ref "C6") (pin "2") (pinfunction "2_2") (pintype "passive"))
      (node (ref "C7") (pin "2") (pinfunction "2_2") (pintype "passive"))
      (node (ref "C8") (pin "2") (pinfunction "2_2") (pintype "passive"))
      (node (ref "C9") (pin "2") (pinfunction "2_2") (pintype "passive"))
      (node (ref "D30") (pin "2") (pinfunction "A_2") (pintype "passive"))
      (node (ref "D31") (pin "2") (pinfunction "A_2") (pintype "passive"))
      (node (ref "J1") (pin "2") (pinfunction "2_2") (pintype "passive"))
      (node (ref "J10") (pin "10") (pinfunction "MH1_10") (pintype "passive"))
      (node (ref "J10") (pin "11") (pinfunction "MH2_11") (pintype "passive"))
      (node (ref "J10") (pin "5") (pinfunction "5_5") (pintype "passive"))
      (node (ref "J3") (pin "3") (pinfunction "3_3") (pintype "passive"))
      (node (ref "JP1") (pin "4") (pinfunction "GND_4") (pintype "passive"))
      (node (ref "JP1") (pin "5") (pinfunction "SHELL_5") (pintype "passive"))
      (node (ref "JP1") (pin "6") (pinfunction "SHELL_6") (pintype "passive"))
      (node (ref "JP2") (pin "1") (pinfunction "1_1") (pintype "passive"))
      (node (ref "JP3") (pin "10") (pinfunction "10_10") (pintype "passive"))
      (node (ref "JP3") (pin "12") (pinfunction "12_12") (pintype "passive"))
      (node (ref "JP3") (pin "14") (pinfunction "14_14") (pintype "passive"))
      (node (ref "JP3") (pin "16") (pinfunction "16_16") (pintype "passive"))
      (node (ref "JP3") (pin "18") (pinfunction "18_18") (pintype "passive"))
      (node (ref "JP3") (pin "20") (pinfunction "20_20") (pintype "passive"))
      (node (ref "JP3") (pin "4") (pinfunction "4_4") (pintype "passive"))
      (node (ref "JP3") (pin "6") (pinfunction "6_6") (pintype "passive"))
      (node (ref "JP3") (pin "8") (pinfunction "8_8") (pintype "passive"))
      (node (ref "JP4") (pin "38") (pinfunction "38_38") (pintype "passive"))
      (node (ref "JP4") (pin "4") (pinfunction "4_4") (pintype "passive"))
      (node (ref "JP4") (pin "40") (pinfunction "40_40") (pintype "passive"))
      (node (ref "JP4") (pin "6") (pinfunction "6_6") (pintype "passive"))
      (node (ref "JP4") (pin "8") (pinfunction "8_8") (pintype "passive"))
      (node (ref "JP5") (pin "10") (pinfunction "10_10") (pintype "passive"))
      (node (ref "JP5") (pin "4") (pinfunction "4_4") (pintype "passive"))
      (node (ref "JP5") (pin "6") (pinfunction "6_6") (pintype "passive"))
      (node (ref "JP5") (pin "8") (pinfunction "8_8") (pintype "passive"))
      (node (ref "M1") (pin "1") (pinfunction "1_1") (pintype "passive"))
      (node (ref "R28") (pin "1") (pinfunction "1_1") (pintype "passive"))
      (node (ref "R54") (pin "1") (pinfunction "1_1") (pintype "passive"))
      (node (ref "R55") (pin "1") (pinfunction "1_1") (pintype "passive"))
      (node (ref "R58") (pin "1") (pinfunction "1_1") (pintype "passive"))
      (node (ref "TP2") (pin "1") (pinfunction "1_1") (pintype "passive"))
      (node (ref "U1") (pin "4") (pinfunction "4_4") (pintype "passive"))
      (node (ref "U10") (pin "4") (pinfunction "4_4") (pintype "passive"))
      (node (ref "U19") (pin "3") (pinfunction "INH_3") (pintype "input"))
      (node (ref "U19") (pin "7") (pinfunction "GND_7") (pintype "power_in"))
      (node (ref "U19") (pin "9") (pinfunction "PAD_GND_9") (pintype "power_in"))
      (node (ref "U2") (pin "4") (pinfunction "4_4") (pintype "passive"))
      (node (ref "U20") (pin "1") (pinfunction "GND_1") (pintype "power_in"))
      (node (ref "U21") (pin "1") (pinfunction "GND_1") (pintype "power_in"))
      (node (ref "U3") (pin "4") (pinfunction "4_4") (pintype "passive"))
      (node (ref "U4") (pin "4") (pinfunction "4_4") (pintype "passive"))
      (node (ref "U5") (pin "4") (pinfunction "4_4") (pintype "passive"))
      (node (ref "U6") (pin "4") (pinfunction "4_4") (pintype "passive"))
      (node (ref "U7") (pin "4") (pinfunction "4_4") (pintype "passive"))
      (node (ref "U8") (pin "4") (pinfunction "4_4") (pintype "passive"))
      (node (ref "U9") (pin "4") (pinfunction "4_4") (pintype "passive"))
    )
    (net (code "43") (name "IN_GND") (class "Default")
      (node (ref "D1") (pin "2") (pinfunction "A_2") (pintype "passive"))
      (node (ref "D10") (pin "2") (pinfunction "A_2") (pintype "passive"))
      (node (ref "D2") (pin "2") (pinfunction "A_2") (pintype "passive"))
      (node (ref "D3") (pin "2") (pinfunction "A_2") (pintype "passive"))
      (node (ref "D4") (pin "2") (pinfunction "A_2") (pintype "passive"))
      (node (ref "D5") (pin "2") (pinfunction "A_2") (pintype "passive"))
      (node (ref "D6") (pin "2") (pinfunction "A_2") (pintype "passive"))
      (node (ref "D7") (pin "2") (pinfunction "A_2") (pintype "passive"))
      (node (ref "D8") (pin "2") (pinfunction "A_2") (pintype "passive"))
      (node (ref "D9") (pin "2") (pinfunction "A_2") (pintype "passive"))
      (node (ref "J6") (pin "1") (pinfunction "1_1") (pintype "passive"))
      (node (ref "JP2") (pin "17") (pinfunction "17_17") (pintype "passive"))
      (node (ref "JP2") (pin "18") (pinfunction "18_18") (pintype "passive"))
    )
    (net (code "44") (name "Net-(C4-Pad1)") (class "Default")
      (node (ref "C4") (pin "1") (pinfunction "1_1") (pintype "passive"))
      (node (ref "R55") (pin "2") (pinfunction "2_2") (pintype "passive"))
    )
    (net (code "45") (name "Net-(D1-C)") (class "Default")
      (node (ref "D1") (pin "1") (pinfunction "C_1") (pintype "passive"))
      (node (ref "D11") (pin "1") (pinfunction "C_1") (pintype "passive"))
      (node (ref "R1") (pin "1") (pinfunction "1_1") (pintype "passive"))
    )
    (net (code "46") (name "Net-(D10-C)") (class "Default")
      (node (ref "D10") (pin "1") (pinfunction "C_1") (pintype "passive"))
      (node (ref "D20") (pin "1") (pinfunction "C_1") (pintype "passive"))
      (node (ref "R10") (pin "1") (pinfunction "1_1") (pintype "passive"))
    )
    (net (code "47") (name "Net-(D11-A)") (class "Default")
      (node (ref "D11") (pin "2") (pinfunction "A_2") (pintype "passive"))
      (node (ref "U1") (pin "1") (pinfunction "1_1") (pintype "passive"))
    )
    (net (code "48") (name "Net-(D12-A)") (class "Default")
      (node (ref "D12") (pin "2") (pinfunction "A_2") (pintype "passive"))
      (node (ref "U2") (pin "1") (pinfunction "1_1") (pintype "passive"))
    )
    (net (code "49") (name "Net-(D12-C)") (class "Default")
      (node (ref "D12") (pin "1") (pinfunction "C_1") (pintype "passive"))
      (node (ref "D2") (pin "1") (pinfunction "C_1") (pintype "passive"))
      (node (ref "R2") (pin "1") (pinfunction "1_1") (pintype "passive"))
    )
    (net (code "50") (name "Net-(D13-A)") (class "Default")
      (node (ref "D13") (pin "2") (pinfunction "A_2") (pintype "passive"))
      (node (ref "U3") (pin "1") (pinfunction "1_1") (pintype "passive"))
    )
    (net (code "51") (name "Net-(D13-C)") (class "Default")
      (node (ref "D13") (pin "1") (pinfunction "C_1") (pintype "passive"))
      (node (ref "D3") (pin "1") (pinfunction "C_1") (pintype "passive"))
      (node (ref "R3") (pin "1") (pinfunction "1_1") (pintype "passive"))
    )
    (net (code "52") (name "Net-(D14-A)") (class "Default")
      (node (ref "D14") (pin "2") (pinfunction "A_2") (pintype "passive"))
      (node (ref "U4") (pin "1") (pinfunction "1_1") (pintype "passive"))
    )
    (net (code "53") (name "Net-(D14-C)") (class "Default")
      (node (ref "D14") (pin "1") (pinfunction "C_1") (pintype "passive"))
      (node (ref "D4") (pin "1") (pinfunction "C_1") (pintype "passive"))
      (node (ref "R4") (pin "1") (pinfunction "1_1") (pintype "passive"))
    )
    (net (code "54") (name "Net-(D15-A)") (class "Default")
      (node (ref "D15") (pin "2") (pinfunction "A_2") (pintype "passive"))
      (node (ref "U5") (pin "1") (pinfunction "1_1") (pintype "passive"))
    )
    (net (code "55") (name "Net-(D15-C)") (class "Default")
      (node (ref "D15") (pin "1") (pinfunction "C_1") (pintype "passive"))
      (node (ref "D5") (pin "1") (pinfunction "C_1") (pintype "passive"))
      (node (ref "R5") (pin "1") (pinfunction "1_1") (pintype "passive"))
    )
    (net (code "56") (name "Net-(D16-A)") (class "Default")
      (node (ref "D16") (pin "2") (pinfunction "A_2") (pintype "passive"))
      (node (ref "U6") (pin "1") (pinfunction "1_1") (pintype "passive"))
    )
    (net (code "57") (name "Net-(D16-C)") (class "Default")
      (node (ref "D16") (pin "1") (pinfunction "C_1") (pintype "passive"))
      (node (ref "D6") (pin "1") (pinfunction "C_1") (pintype "passive"))
      (node (ref "R6") (pin "1") (pinfunction "1_1") (pintype "passive"))
    )
    (net (code "58") (name "Net-(D17-A)") (class "Default")
      (node (ref "D17") (pin "2") (pinfunction "A_2") (pintype "passive"))
      (node (ref "U7") (pin "1") (pinfunction "1_1") (pintype "passive"))
    )
    (net (code "59") (name "Net-(D17-C)") (class "Default")
      (node (ref "D17") (pin "1") (pinfunction "C_1") (pintype "passive"))
      (node (ref "D7") (pin "1") (pinfunction "C_1") (pintype "passive"))
      (node (ref "R7") (pin "1") (pinfunction "1_1") (pintype "passive"))
    )
    (net (code "60") (name "Net-(D18-A)") (class "Default")
      (node (ref "D18") (pin "2") (pinfunction "A_2") (pintype "passive"))
      (node (ref "U8") (pin "1") (pinfunction "1_1") (pintype "passive"))
    )
    (net (code "61") (name "Net-(D18-C)") (class "Default")
      (node (ref "D18") (pin "1") (pinfunction "C_1") (pintype "passive"))
      (node (ref "D8") (pin "1") (pinfunction "C_1") (pintype "passive"))
      (node (ref "R8") (pin "1") (pinfunction "1_1") (pintype "passive"))
    )
    (net (code "62") (name "Net-(D19-A)") (class "Default")
      (node (ref "D19") (pin "2") (pinfunction "A_2") (pintype "passive"))
      (node (ref "U9") (pin "1") (pinfunction "1_1") (pintype "passive"))
    )
    (net (code "63") (name "Net-(D19-C)") (class "Default")
      (node (ref "D19") (pin "1") (pinfunction "C_1") (pintype "passive"))
      (node (ref "D9") (pin "1") (pinfunction "C_1") (pintype "passive"))
      (node (ref "R9") (pin "1") (pinfunction "1_1") (pintype "passive"))
    )
    (net (code "64") (name "Net-(D20-A)") (class "Default")
      (node (ref "D20") (pin "2") (pinfunction "A_2") (pintype "passive"))
      (node (ref "U10") (pin "1") (pinfunction "1_1") (pintype "passive"))
    )
    (net (code "65") (name "Net-(D29-A)") (class "Default")
      (node (ref "D29") (pin "2") (pinfunction "A_2") (pintype "passive"))
      (node (ref "D31") (pin "1") (pinfunction "C_1") (pintype "passive"))
      (node (ref "F1") (pin "2") (pinfunction "2_2") (pintype "passive"))
      (node (ref "M1") (pin "2") (pinfunction "2_2") (pintype "passive"))
    )
    (net (code "66") (name "Net-(D30-C)") (class "Default")
      (node (ref "D30") (pin "1") (pinfunction "C_1") (pintype "passive"))
      (node (ref "L1") (pin "1") (pinfunction "1_1") (pintype "passive"))
      (node (ref "U19") (pin "1") (pinfunction "OUT_1") (pintype "output"))
    )
    (net (code "67") (name "Net-(J3-Pad1)") (class "Default")
      (node (ref "J3") (pin "1") (pinfunction "1_1") (pintype "passive"))
      (node (ref "R2") (pin "2") (pinfunction "2_2") (pintype "passive"))
    )
    (net (code "68") (name "Net-(J3-Pad2)") (class "Default")
      (node (ref "J3") (pin "2") (pinfunction "2_2") (pintype "passive"))
      (node (ref "R1") (pin "2") (pinfunction "2_2") (pintype "passive"))
    )
    (net (code "69") (name "Net-(J4-Pad1)") (class "Default")
      (node (ref "J4") (pin "1") (pinfunction "1_1") (pintype "passive"))
      (node (ref "R5") (pin "2") (pinfunction "2_2") (pintype "passive"))
    )
    (net (code "70") (name "Net-(J4-Pad2)") (class "Default")
      (node (ref "J4") (pin "2") (pinfunction "2_2") (pintype "passive"))
      (node (ref "R4") (pin "2") (pinfunction "2_2") (pintype "passive"))
    )
    (net (code "71") (name "Net-(J4-Pad3)") (class "Default")
      (node (ref "J4") (pin "3") (pinfunction "3_3") (pintype "passive"))
      (node (ref "R3") (pin "2") (pinfunction "2_2") (pintype "passive"))
    )
    (net (code "72") (name "Net-(J5-Pad1)") (class "Default")
      (node (ref "J5") (pin "1") (pinfunction "1_1") (pintype "passive"))
      (node (ref "R8") (pin "2") (pinfunction "2_2") (pintype "passive"))
    )
    (net (code "73") (name "Net-(J5-Pad2)") (class "Default")
      (node (ref "J5") (pin "2") (pinfunction "2_2") (pintype "passive"))
      (node (ref "R7") (pin "2") (pinfunction "2_2") (pintype "passive"))
    )
    (net (code "74") (name "Net-(J5-Pad3)") (class "Default")
      (node (ref "J5") (pin "3") (pinfunction "3_3") (pintype "passive"))
      (node (ref "R6") (pin "2") (pinfunction "2_2") (pintype "passive"))
    )
    (net (code "75") (name "Net-(J6-Pad2)") (class "Default")
      (node (ref "J6") (pin "2") (pinfunction "2_2") (pintype "passive"))
      (node (ref "R10") (pin "2") (pinfunction "2_2") (pintype "passive"))
    )
    (net (code "76") (name "Net-(J6-Pad3)") (class "Default")
      (node (ref "J6") (pin "3") (pinfunction "3_3") (pintype "passive"))
      (node (ref "R9") (pin "2") (pinfunction "2_2") (pintype "passive"))
    )
    (net (code "77") (name "Net-(J10-Pad4)") (class "Default")
      (node (ref "J10") (pin "4") (pinfunction "4_4") (pintype "passive"))
      (node (ref "JP6") (pin "1") (pinfunction "1_1") (pintype "passive"))
    )
    (net (code "78") (name "Net-(JP1-D+)") (class "Default")
      (node (ref "JP1") (pin "3") (pinfunction "D+_3") (pintype "passive"))
      (node (ref "R57") (pin "1") (pinfunction "1_1") (pintype "passive"))
    )
    (net (code "79") (name "Net-(JP1-D-)") (class "Default")
      (node (ref "JP1") (pin "2") (pinfunction "D-_2") (pintype "passive"))
      (node (ref "R56") (pin "1") (pinfunction "1_1") (pintype "passive"))
    )
    (net (code "80") (name "Net-(JP1-VCC)") (class "Default")
      (node (ref "JP1") (pin "1") (pinfunction "VCC_1") (pintype "passive"))
      (node (ref "JP7") (pin "1") (pinfunction "1_1") (pintype "passive"))
      (node (ref "R25") (pin "1") (pinfunction "1_1") (pintype "passive"))
    )
    (net (code "81") (name "Net-(JP3-Pad3)") (class "Default")
      (node (ref "JP3") (pin "3") (pinfunction "3_3") (pintype "passive"))
      (node (ref "R47") (pin "1") (pinfunction "1_1") (pintype "passive"))
    )
    (net (code "82") (name "Net-(Q9-B)") (class "Default")
      (node (ref "Q9") (pin "1") (pinfunction "B_1") (pintype "passive"))
      (node (ref "R48") (pin "2") (pinfunction "2_2") (pintype "passive"))
    )
    (net (code "83") (name "Net-(Q9-C)") (class "Default")
      (node (ref "Q9") (pin "3") (pinfunction "C_3") (pintype "passive"))
      (node (ref "R50") (pin "2") (pinfunction "2_2") (pintype "passive"))
    )
    (net (code "84") (name "Net-(Q10-G)") (class "Default")
      (node (ref "Q10") (pin "1") (pinfunction "G_1") (pintype "passive"))
      (node (ref "R51") (pin "2") (pinfunction "2_2") (pintype "passive"))
    )
    (net (code "85") (name "Net-(Q10-S)") (class "Default")
      (node (ref "Q10") (pin "2") (pinfunction "S_2") (pintype "passive"))
      (node (ref "R52") (pin "2") (pinfunction "2_2") (pintype "passive"))
    )
    (net (code "86") (name "Net-(U19-COMP)") (class "Default")
      (node (ref "C10") (pin "2") (pinfunction "2_2") (pintype "passive"))
      (node (ref "C4") (pin "2") (pinfunction "2_2") (pintype "passive"))
      (node (ref "U19") (pin "4") (pinfunction "COMP_4") (pintype "output"))
    )
    (net (code "87") (name "Net-(U19-FB)") (class "Default")
      (node (ref "R53") (pin "1") (pinfunction "1_1") (pintype "passive"))
      (node (ref "R58") (pin "2") (pinfunction "2_2") (pintype "passive"))
      (node (ref "U19") (pin "5") (pinfunction "FB_5") (pintype "input"))
    )
    (net (code "88") (name "Net-(U19-VREF)") (class "Default")
      (node (ref "TP1") (pin "1") (pinfunction "1_1") (pintype "passive"))
      (node (ref "U19") (pin "6") (pinfunction "VREF_6") (pintype "output"))
    )
    (net (code "89") (name "PA0") (class "Default")
      (node (ref "JP4") (pin "32") (pinfunction "32_32") (pintype "passive"))
    )
    (net (code "90") (name "PA1") (class "Default")
      (node (ref "JP4") (pin "33") (pinfunction "33_33") (pintype "passive"))
    )
    (net (code "91") (name "PA2") (class "Default")
      (node (ref "JP4") (pin "34") (pinfunction "34_34") (pintype "passive"))
    )
    (net (code "92") (name "PA27") (class "Default")
      (node (ref "JP4") (pin "27") (pinfunction "27_27") (pintype "passive"))
    )
    (net (code "93") (name "PA28") (class "Default")
      (node (ref "JP4") (pin "28") (pinfunction "28_28") (pintype "passive"))
    )
    (net (code "94") (name "PA29") (class "Default")
      (node (ref "JP4") (pin "29") (pinfunction "29_29") (pintype "passive"))
    )
    (net (code "95") (name "PA30") (class "Default")
      (node (ref "JP4") (pin "30") (pinfunction "30_30") (pintype "passive"))
    )
    (net (code "96") (name "PA31") (class "Default")
      (node (ref "JP4") (pin "31") (pinfunction "31_31") (pintype "passive"))
    )
    (net (code "97") (name "VCC3v3") (class "Default")
      (node (ref "C5") (pin "1") (pinfunction "1_1") (pintype "passive"))
      (node (ref "C7") (pin "1") (pinfunction "1_1") (pintype "passive"))
      (node (ref "C9") (pin "1") (pinfunction "1_1") (pintype "passive"))
      (node (ref "JP2") (pin "5") (pinfunction "5_5") (pintype "passive"))
      (node (ref "JP3") (pin "1") (pinfunction "1_1") (pintype "passive"))
      (node (ref "JP3") (pin "2") (pinfunction "2_2") (pintype "passive"))
      (node (ref "JP4") (pin "1") (pinfunction "1_1") (pintype "passive"))
      (node (ref "JP4") (pin "2") (pinfunction "2_2") (pintype "passive"))
      (node (ref "Q10") (pin "3") (pinfunction "D_3") (pintype "passive"))
      (node (ref "Q9") (pin "2") (pinfunction "E_2") (pintype "passive"))
      (node (ref "R11") (pin "2") (pinfunction "2_2") (pintype "passive"))
      (node (ref "R12") (pin "2") (pinfunction "2_2") (pintype "passive"))
      (node (ref "R13") (pin "2") (pinfunction "2_2") (pintype "passive"))
      (node (ref "R14") (pin "2") (pinfunction "2_2") (pintype "passive"))
      (node (ref "R15") (pin "2") (pinfunction "2_2") (pintype "passive"))
      (node (ref "R16") (pin "2") (pinfunction "2_2") (pintype "passive"))
      (node (ref "R17") (pin "2") (pinfunction "2_2") (pintype "passive"))
      (node (ref "R18") (pin "2") (pinfunction "2_2") (pintype "passive"))
      (node (ref "R19") (pin "2") (pinfunction "2_2") (pintype "passive"))
      (node (ref "R20") (pin "2") (pinfunction "2_2") (pintype "passive"))
      (node (ref "R47") (pin "2") (pinfunction "2_2") (pintype "passive"))
      (node (ref "R49") (pin "2") (pinfunction "2_2") (pintype "passive"))
      (node (ref "U20") (pin "2") (pinfunction "VOUT_2") (pintype "power_in"))
      (node (ref "U20") (pin "4") (pinfunction "VOUT_4") (pintype "power_in"))
      (node (ref "U21") (pin "2") (pinfunction "OUT_2") (pintype "power_in"))
    )
    (net (code "98") (name "VCC5") (class "Default")
      (node (ref "C3") (pin "1") (pinfunction "1_1") (pintype "passive"))
      (node (ref "C6") (pin "1") (pinfunction "1_1") (pintype "passive"))
      (node (ref "C8") (pin "1") (pinfunction "1_1") (pintype "passive"))
      (node (ref "JP6") (pin "2") (pinfunction "2_2") (pintype "passive"))
      (node (ref "JP7") (pin "2") (pinfunction "2_2") (pintype "passive"))
      (node (ref "L1") (pin "2") (pinfunction "2_2") (pintype "passive"))
      (node (ref "R53") (pin "2") (pinfunction "2_2") (pintype "passive"))
      (node (ref "U20") (pin "3") (pinfunction "VIN_3") (pintype "power_in"))
      (node (ref "U21") (pin "3") (pinfunction "IN_3") (pintype "power_in"))
    )
    (net (code "99") (name "VCC24") (class "Default")
      (node (ref "F1") (pin "1") (pinfunction "1_1") (pintype "passive"))
      (node (ref "J1") (pin "3") (pinfunction "3_3") (pintype "passive"))
    )
    (net (code "100") (name "unconnected-(J10-Pad1)") (class "Default")
      (node (ref "J10") (pin "1") (pinfunction "1_1") (pintype "passive+no_connect"))
    )
    (net (code "101") (name "unconnected-(J10-Pad2)") (class "Default")
      (node (ref "J10") (pin "2") (pinfunction "2_2") (pintype "passive+no_connect"))
    )
    (net (code "102") (name "unconnected-(J10-Pad3)") (class "Default")
      (node (ref "J10") (pin "3") (pinfunction "3_3") (pintype "passive+no_connect"))
    )
    (net (code "103") (name "unconnected-(J10-Pad8)") (class "Default")
      (node (ref "J10") (pin "8") (pinfunction "8_8") (pintype "passive+no_connect"))
    )
    (net (code "104") (name "unconnected-(J10-Pad9)") (class "Default")
      (node (ref "J10") (pin "9") (pinfunction "9_9") (pintype "passive+no_connect"))
    )
    (net (code "105") (name "unconnected-(JP3-Pad17)") (class "Default")
      (node (ref "JP3") (pin "17") (pinfunction "17_17") (pintype "passive+no_connect"))
    )
    (net (code "106") (name "unconnected-(JP3-Pad19)") (class "Default")
      (node (ref "JP3") (pin "19") (pinfunction "19_19") (pintype "passive+no_connect"))
    )
    (net (code "107") (name "unconnected-(JP4-Pad21)") (class "Default")
      (node (ref "JP4") (pin "21") (pinfunction "21_21") (pintype "passive+no_connect"))
    )
    (net (code "108") (name "unconnected-(JP4-Pad23)") (class "Default")
      (node (ref "JP4") (pin "23") (pinfunction "23_23") (pintype "passive+no_connect"))
    )
    (net (code "109") (name "unconnected-(U19-SYNC-Pad2)") (class "Default")
      (node (ref "U19") (pin "2") (pinfunction "SYNC_2") (pintype "input+no_connect"))
    )
  )
)
